# led-module.net
KiCad netlist of a schematic drawn in EAGLE
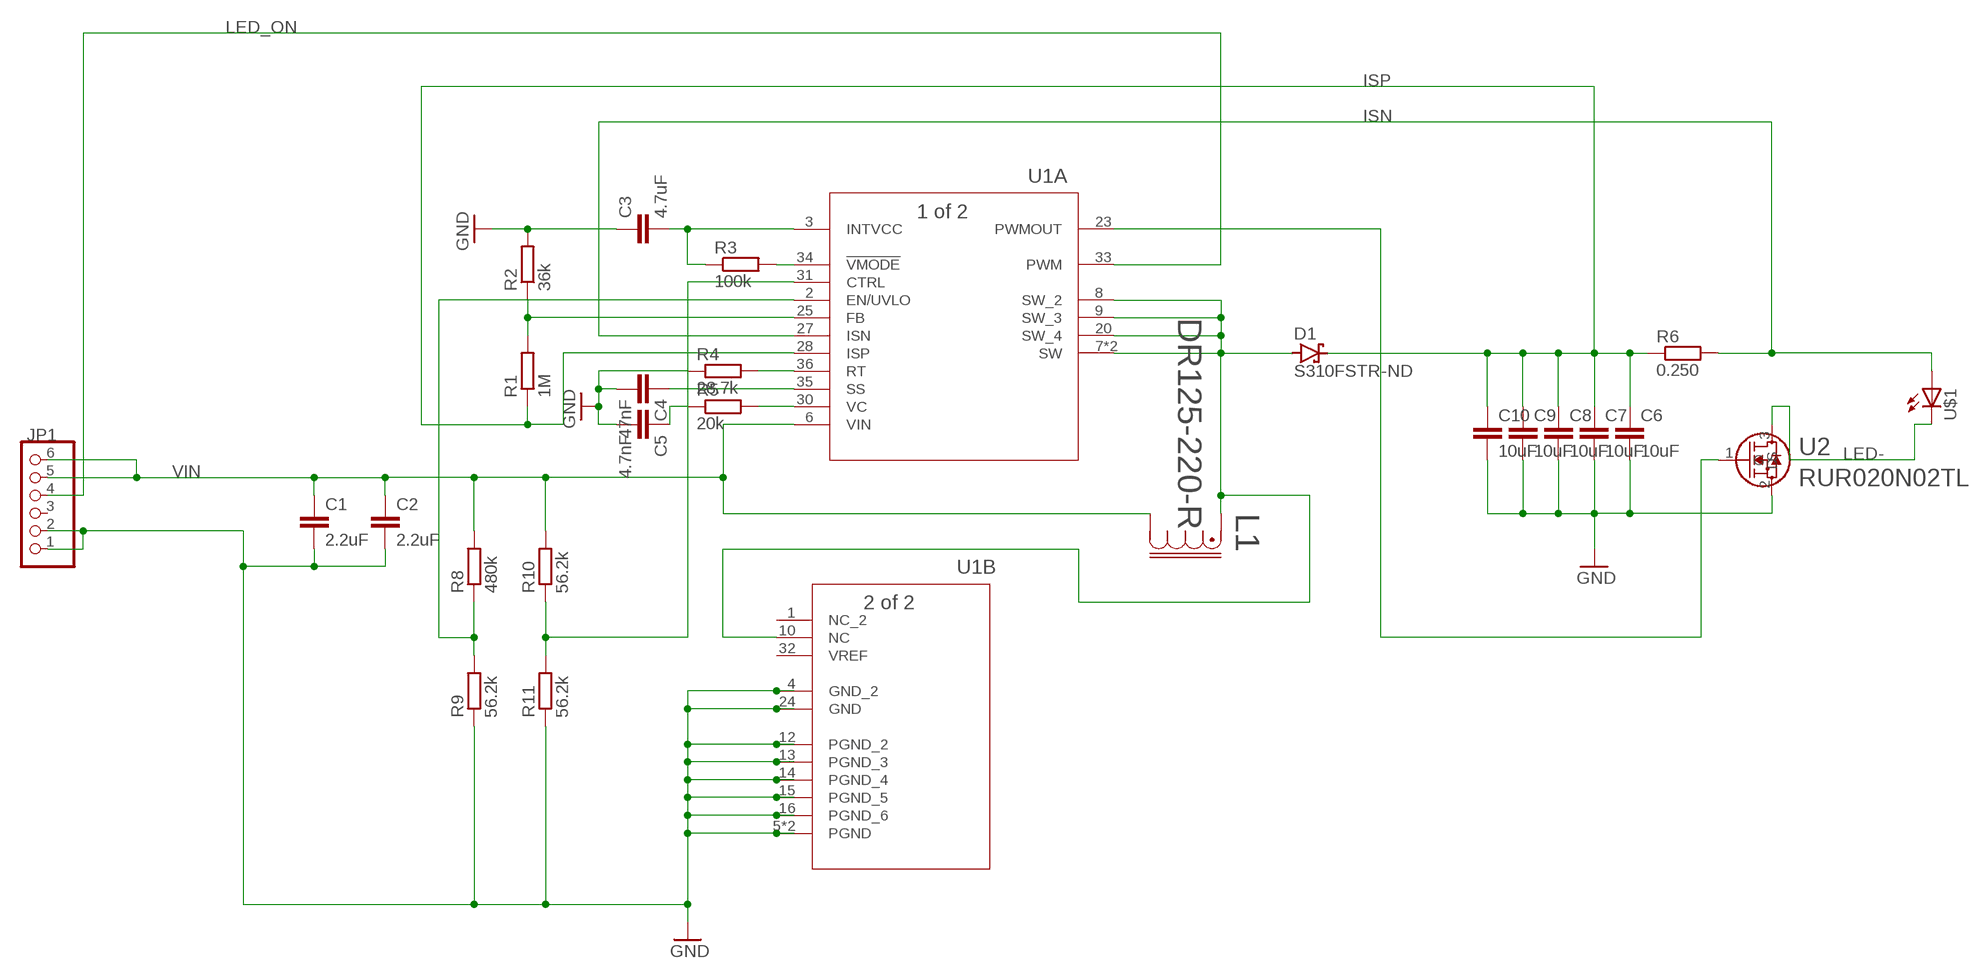
[diagram p0: schematic, sheet 1]

(export (version "E")
  (design (tool "Eeschema 10.0.6"))
  (components
    (comp (ref "C1")
      (value "2.2uF")
      (footprint "eagle-import:C0805")
      (libsource (lib "eagle-import") (part "C-EUC0805"))
    )
    (comp (ref "C2")
      (value "2.2uF")
      (footprint "eagle-import:C0805")
      (libsource (lib "eagle-import") (part "C-EUC0805"))
    )
    (comp (ref "C3")
      (value "4.7uF")
      (footprint "eagle-import:C0402")
      (libsource (lib "eagle-import") (part "C-EUC0402"))
    )
    (comp (ref "C4")
      (value "47nF")
      (footprint "eagle-import:C0402")
      (libsource (lib "eagle-import") (part "C-EUC0402"))
    )
    (comp (ref "C5")
      (value "4.7nF")
      (footprint "eagle-import:C0402")
      (libsource (lib "eagle-import") (part "C-EUC0402"))
    )
    (comp (ref "C6")
      (value "10uF")
      (footprint "eagle-import:C0805")
      (libsource (lib "eagle-import") (part "C-EUC0805"))
    )
    (comp (ref "C7")
      (value "10uF")
      (footprint "eagle-import:C0805")
      (libsource (lib "eagle-import") (part "C-EUC0805"))
    )
    (comp (ref "C8")
      (value "10uF")
      (footprint "eagle-import:C0805")
      (libsource (lib "eagle-import") (part "C-EUC0805"))
    )
    (comp (ref "C9")
      (value "10uF")
      (footprint "eagle-import:C0805")
      (libsource (lib "eagle-import") (part "C-EUC0805"))
    )
    (comp (ref "C10")
      (value "10uF")
      (footprint "eagle-import:C0805")
      (libsource (lib "eagle-import") (part "C-EUC0805"))
    )
    (comp (ref "D1")
      (value "S310FSTR-ND")
      (footprint "eagle-import:SMC")
      (libsource (lib "eagle-import") (part "SCHOTTKY-DIODESMC"))
    )
    (comp (ref "JP1")
      (value "PINHD-1X6")
      (footprint "eagle-import:1X06")
      (libsource (lib "eagle-import") (part "PINHD-1X6"))
    )
    (comp (ref "L1")
      (value "DR125-220-R")
      (footprint "eagle-import:DR125")
      (fields (field (name "COPYRIGHT") "Copyright (C) 2021 Ultra Librarian. All rights reserved."))
      (libsource (lib "eagle-import") (part "DR125-220-R"))
    )
    (comp (ref "R1")
      (value "1M")
      (footprint "eagle-import:R0402")
      (libsource (lib "eagle-import") (part "R-EU_R0402"))
    )
    (comp (ref "R2")
      (value "36k")
      (footprint "eagle-import:R0402")
      (libsource (lib "eagle-import") (part "R-EU_R0402"))
    )
    (comp (ref "R3")
      (value "100k")
      (footprint "eagle-import:R0402")
      (libsource (lib "eagle-import") (part "R-EU_R0402"))
    )
    (comp (ref "R4")
      (value "28.7k")
      (footprint "eagle-import:R0402")
      (libsource (lib "eagle-import") (part "R-EU_R0402"))
    )
    (comp (ref "R5")
      (value "20k")
      (footprint "eagle-import:R0402")
      (libsource (lib "eagle-import") (part "R-EU_R0402"))
    )
    (comp (ref "R6")
      (value "0.250")
      (footprint "eagle-import:WSC2515")
      (libsource (lib "eagle-import") (part "R-EU_WSC2515"))
    )
    (comp (ref "R8")
      (value "480k")
      (footprint "eagle-import:R0402")
      (libsource (lib "eagle-import") (part "R-EU_R0402"))
    )
    (comp (ref "R9")
      (value "56.2k")
      (footprint "eagle-import:R0402")
      (libsource (lib "eagle-import") (part "R-EU_R0402"))
    )
    (comp (ref "R10")
      (value "56.2k")
      (footprint "eagle-import:R0402")
      (libsource (lib "eagle-import") (part "R-EU_R0402"))
    )
    (comp (ref "R11")
      (value "56.2k")
      (footprint "eagle-import:R0402")
      (libsource (lib "eagle-import") (part "R-EU_R0402"))
    )
    (comp (ref "U$1")
      (value "5-2154874-3")
      (footprint "eagle-import:5-2154874-3")
      (libsource (lib "eagle-import") (part "5-2154874-3"))
    )
    (comp (ref "U1")
      (value "LT3956EUHEPBFUHE_36_ADI-M")
      (footprint "eagle-import:UHE_36_ADI-M")
      (fields
        (field (name "MANUFACTURER_PART_NUMBER") "LT3956EUHE#PBF")
        (field (name "COPYRIGHT") "Copyright (C) 2021 Ultra Librarian. All rights reserved.")
      )
      (libsource (lib "eagle-import") (part "LT3956EUHEPBFUHE_36_ADI-M"))
    )
    (comp (ref "U2")
      (value "RUR020N02TL")
      (footprint "eagle-import:TRANS_RTR020N_ROM")
      (fields (field (name "COPYRIGHT") "Copyright (C) 2021 Ultra Librarian. All rights reserved."))
      (libsource (lib "eagle-import") (part "RUR020N02TL"))
    )
  )
  (nets
    (net (code "1") (name "/ISN") (class "Default")
      (node (ref "R6") (pin "2") (pinfunction "2_2") (pintype "passive"))
      (node (ref "U$1") (pin "P$1") (pinfunction "A_P$1") (pintype "passive"))
      (node (ref "U1") (pin "27") (pinfunction "ISN_27") (pintype "passive"))
    )
    (net (code "2") (name "/ISP") (class "Default")
      (node (ref "C10") (pin "1") (pinfunction "1_1") (pintype "passive"))
      (node (ref "C6") (pin "1") (pinfunction "1_1") (pintype "passive"))
      (node (ref "C7") (pin "1") (pinfunction "1_1") (pintype "passive"))
      (node (ref "C8") (pin "1") (pinfunction "1_1") (pintype "passive"))
      (node (ref "C9") (pin "1") (pinfunction "1_1") (pintype "passive"))
      (node (ref "D1") (pin "C") (pinfunction "C_C") (pintype "passive"))
      (node (ref "R1") (pin "1") (pinfunction "1_1") (pintype "passive"))
      (node (ref "R6") (pin "1") (pinfunction "1_1") (pintype "passive"))
      (node (ref "U1") (pin "28") (pinfunction "ISP_28") (pintype "passive"))
    )
    (net (code "3") (name "/LED-") (class "Default")
      (node (ref "U$1") (pin "P$2") (pinfunction "C_P$2") (pintype "passive"))
      (node (ref "U2") (pin "3") (pinfunction "D_3") (pintype "passive"))
    )
    (net (code "4") (name "/LED_ON") (class "Default")
      (node (ref "JP1") (pin "4") (pinfunction "4_4") (pintype "passive"))
      (node (ref "U1") (pin "33") (pinfunction "PWM_33") (pintype "passive"))
    )
    (net (code "5") (name "/VIN") (class "Default")
      (node (ref "C1") (pin "1") (pinfunction "1_1") (pintype "passive"))
      (node (ref "C2") (pin "1") (pinfunction "1_1") (pintype "passive"))
      (node (ref "JP1") (pin "5") (pinfunction "5_5") (pintype "passive"))
      (node (ref "JP1") (pin "6") (pinfunction "6_6") (pintype "passive"))
      (node (ref "L1") (pin "2") (pinfunction "2_2") (pintype "passive"))
      (node (ref "R10") (pin "2") (pinfunction "2_2") (pintype "passive"))
      (node (ref "R8") (pin "2") (pinfunction "2_2") (pintype "passive"))
      (node (ref "U1") (pin "6") (pinfunction "VIN_6") (pintype "passive"))
    )
    (net (code "6") (name "GND") (class "Default")
      (node (ref "C1") (pin "2") (pinfunction "2_2") (pintype "passive"))
      (node (ref "C10") (pin "2") (pinfunction "2_2") (pintype "passive"))
      (node (ref "C2") (pin "2") (pinfunction "2_2") (pintype "passive"))
      (node (ref "C3") (pin "1") (pinfunction "1_1") (pintype "passive"))
      (node (ref "C4") (pin "2") (pinfunction "2_2") (pintype "passive"))
      (node (ref "C5") (pin "2") (pinfunction "2_2") (pintype "passive"))
      (node (ref "C6") (pin "2") (pinfunction "2_2") (pintype "passive"))
      (node (ref "C7") (pin "2") (pinfunction "2_2") (pintype "passive"))
      (node (ref "C8") (pin "2") (pinfunction "2_2") (pintype "passive"))
      (node (ref "C9") (pin "2") (pinfunction "2_2") (pintype "passive"))
      (node (ref "JP1") (pin "1") (pinfunction "1_1") (pintype "passive"))
      (node (ref "JP1") (pin "2") (pinfunction "2_2") (pintype "passive"))
      (node (ref "R11") (pin "1") (pinfunction "1_1") (pintype "passive"))
      (node (ref "R2") (pin "2") (pinfunction "2_2") (pintype "passive"))
      (node (ref "R4") (pin "1") (pinfunction "1_1") (pintype "passive"))
      (node (ref "R9") (pin "1") (pinfunction "1_1") (pintype "passive"))
      (node (ref "U1") (pin "12") (pinfunction "PGND_2_12") (pintype "passive"))
      (node (ref "U1") (pin "13") (pinfunction "PGND_3_13") (pintype "passive"))
      (node (ref "U1") (pin "14") (pinfunction "PGND_4_14") (pintype "passive"))
      (node (ref "U1") (pin "15") (pinfunction "PGND_5_15") (pintype "passive"))
      (node (ref "U1") (pin "16") (pinfunction "PGND_6_16") (pintype "passive"))
      (node (ref "U1") (pin "17") (pinfunction "PGND_17") (pintype "passive"))
      (node (ref "U1") (pin "24") (pinfunction "GND_24") (pintype "passive"))
      (node (ref "U1") (pin "4") (pinfunction "GND_2_4") (pintype "passive"))
      (node (ref "U1") (pin "5") (pinfunction "PGND_5") (pintype "passive"))
      (node (ref "U2") (pin "2") (pinfunction "S_2") (pintype "passive"))
    )
    (net (code "7") (name "Net-(C5-Pad1)") (class "Default")
      (node (ref "C5") (pin "1") (pinfunction "1_1") (pintype "passive"))
      (node (ref "R5") (pin "1") (pinfunction "1_1") (pintype "passive"))
    )
    (net (code "8") (name "Net-(U1A-CTRL)") (class "Default")
      (node (ref "R10") (pin "1") (pinfunction "1_1") (pintype "passive"))
      (node (ref "R11") (pin "2") (pinfunction "2_2") (pintype "passive"))
      (node (ref "U1") (pin "31") (pinfunction "CTRL_31") (pintype "passive"))
    )
    (net (code "9") (name "Net-(U1A-EN{slash}UVLO)") (class "Default")
      (node (ref "R8") (pin "1") (pinfunction "1_1") (pintype "passive"))
      (node (ref "R9") (pin "2") (pinfunction "2_2") (pintype "passive"))
      (node (ref "U1") (pin "2") (pinfunction "EN/UVLO_2") (pintype "passive"))
    )
    (net (code "10") (name "Net-(U1A-FB)") (class "Default")
      (node (ref "R1") (pin "2") (pinfunction "2_2") (pintype "passive"))
      (node (ref "R2") (pin "1") (pinfunction "1_1") (pintype "passive"))
      (node (ref "U1") (pin "25") (pinfunction "FB_25") (pintype "passive"))
    )
    (net (code "11") (name "Net-(U1A-INTVCC)") (class "Default")
      (node (ref "C3") (pin "2") (pinfunction "2_2") (pintype "passive"))
      (node (ref "R3") (pin "1") (pinfunction "1_1") (pintype "passive"))
      (node (ref "U1") (pin "3") (pinfunction "INTVCC_3") (pintype "passive"))
    )
    (net (code "12") (name "Net-(U1A-PWMOUT)") (class "Default")
      (node (ref "U1") (pin "23") (pinfunction "PWMOUT_23") (pintype "passive"))
      (node (ref "U2") (pin "1") (pinfunction "G_1") (pintype "passive"))
    )
    (net (code "13") (name "Net-(U1A-RT)") (class "Default")
      (node (ref "R4") (pin "2") (pinfunction "2_2") (pintype "passive"))
      (node (ref "U1") (pin "36") (pinfunction "RT_36") (pintype "passive"))
    )
    (net (code "14") (name "Net-(U1A-SS)") (class "Default")
      (node (ref "C4") (pin "1") (pinfunction "1_1") (pintype "passive"))
      (node (ref "U1") (pin "35") (pinfunction "SS_35") (pintype "passive"))
    )
    (net (code "15") (name "Net-(U1A-SW_2)") (class "Default")
      (node (ref "D1") (pin "A") (pinfunction "A_A") (pintype "passive"))
      (node (ref "L1") (pin "1") (pinfunction "1_1") (pintype "passive"))
      (node (ref "U1") (pin "10") (pinfunction "NC_10") (pintype "passive"))
      (node (ref "U1") (pin "20") (pinfunction "SW_4_20") (pintype "passive"))
      (node (ref "U1") (pin "21") (pinfunction "SW_21") (pintype "passive"))
      (node (ref "U1") (pin "7") (pinfunction "SW_7") (pintype "passive"))
      (node (ref "U1") (pin "8") (pinfunction "SW_2_8") (pintype "passive"))
      (node (ref "U1") (pin "9") (pinfunction "SW_3_9") (pintype "passive"))
    )
    (net (code "16") (name "Net-(U1A-VC)") (class "Default")
      (node (ref "R5") (pin "2") (pinfunction "2_2") (pintype "passive"))
      (node (ref "U1") (pin "30") (pinfunction "VC_30") (pintype "passive"))
    )
    (net (code "17") (name "Net-(U1A-~{VMODE})") (class "Default")
      (node (ref "R3") (pin "2") (pinfunction "2_2") (pintype "passive"))
      (node (ref "U1") (pin "34") (pinfunction "~{VMODE}_34") (pintype "passive"))
    )
    (net (code "18") (name "unconnected-(JP1-Pad3)") (class "Default")
      (node (ref "JP1") (pin "3") (pinfunction "3_3") (pintype "passive"))
    )
    (net (code "19") (name "unconnected-(U1B-NC_2-Pad1)") (class "Default")
      (node (ref "U1") (pin "1") (pinfunction "NC_2_1") (pintype "passive"))
    )
    (net (code "20") (name "unconnected-(U1B-VREF-Pad32)") (class "Default")
      (node (ref "U1") (pin "32") (pinfunction "VREF_32") (pintype "passive"))
    )
  )
)
